# Sheet1.net
KiCad netlist of a schematic drawn in Altium Designer
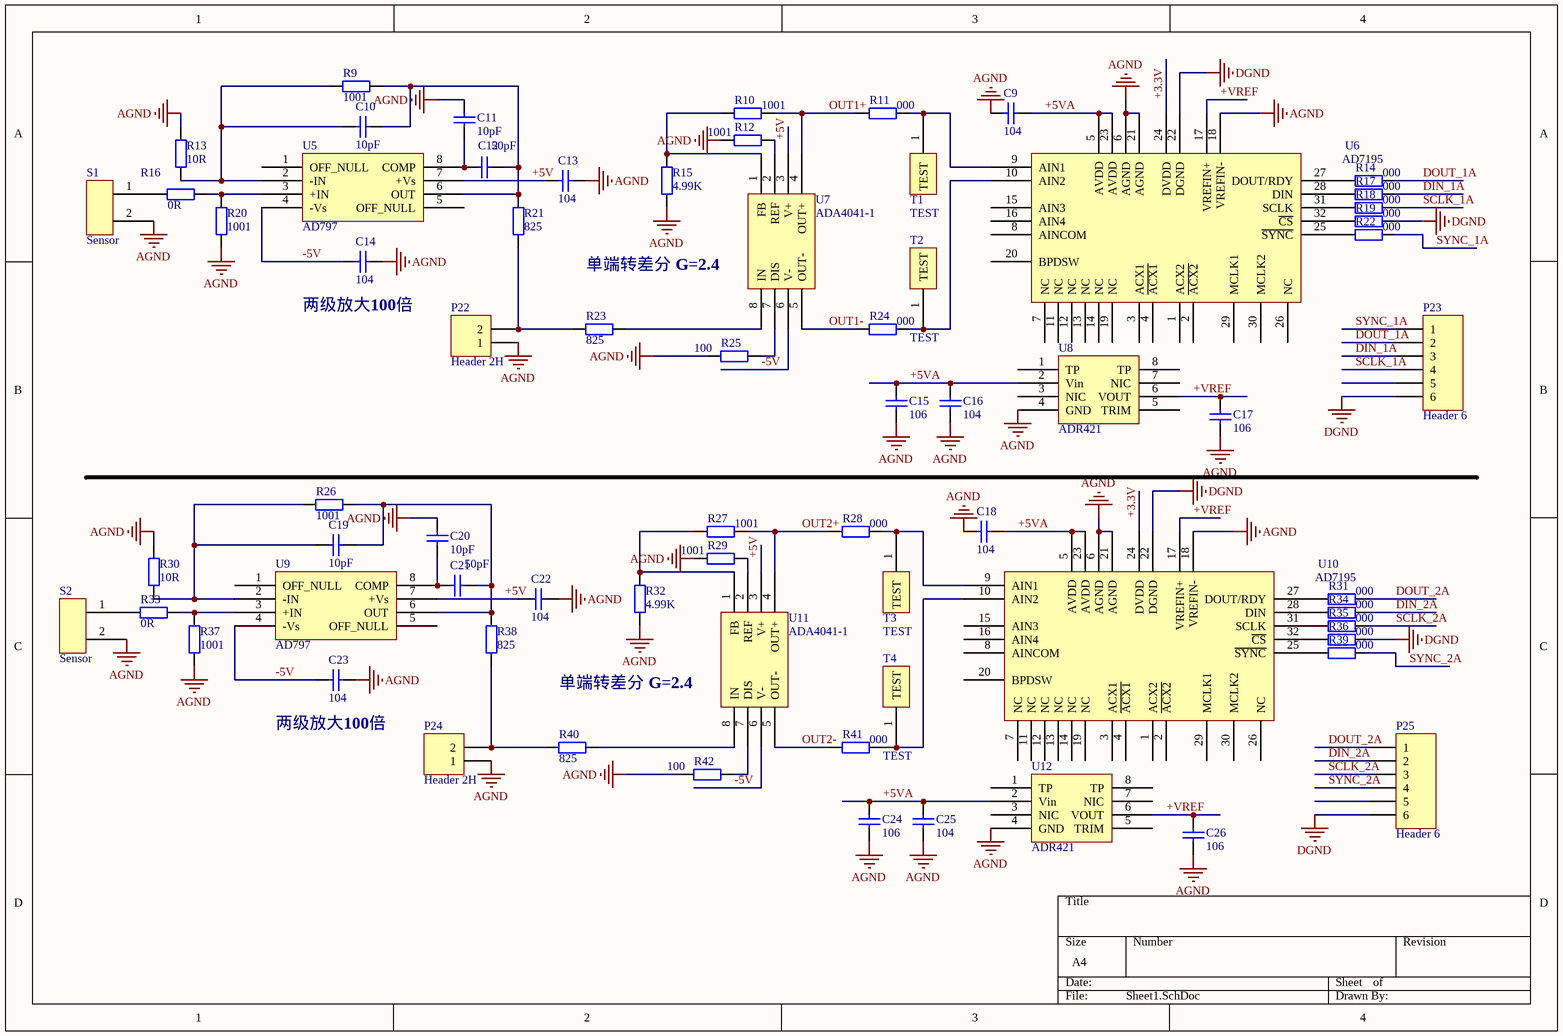
[diagram p0: Sheet1.SchDoc]

(export (version "E")
  (design (tool "Eeschema 10.0.6"))
  (components
    (comp (ref "C9")
      (value "104")
      (footprint "0805C")
      (description "Capacitor")
      (fields (field (name "PUBLISHER") "Altium Limited"))
      (libsource (lib "Miscellaneous Devices") (part "Cap"))
    )
    (comp (ref "C10")
      (value "10pF")
      (footprint "0805C")
      (description "Capacitor")
      (fields (field (name "PUBLISHER") "Altium Limited"))
      (libsource (lib "Miscellaneous Devices") (part "Cap"))
    )
    (comp (ref "C11")
      (value "10pF")
      (footprint "0805C")
      (description "Capacitor")
      (fields (field (name "PUBLISHER") "Altium Limited"))
      (libsource (lib "Miscellaneous Devices") (part "Cap"))
    )
    (comp (ref "C12")
      (value "50pF")
      (footprint "0805C")
      (description "Capacitor")
      (fields (field (name "PUBLISHER") "Altium Limited"))
      (libsource (lib "Miscellaneous Devices") (part "Cap"))
    )
    (comp (ref "C13")
      (value "104")
      (footprint "0805C")
      (description "Capacitor")
      (fields (field (name "PUBLISHER") "Altium Limited"))
      (libsource (lib "Miscellaneous Devices") (part "Cap"))
    )
    (comp (ref "C14")
      (value "104")
      (footprint "0805C")
      (description "Capacitor")
      (fields (field (name "PUBLISHER") "Altium Limited"))
      (libsource (lib "Miscellaneous Devices") (part "Cap"))
    )
    (comp (ref "C15")
      (value "106")
      (footprint "0805C")
      (description "Capacitor")
      (fields (field (name "PUBLISHER") "Altium Limited"))
      (libsource (lib "Miscellaneous Devices") (part "Cap"))
    )
    (comp (ref "C16")
      (value "104")
      (footprint "0805C")
      (description "Capacitor")
      (fields (field (name "PUBLISHER") "Altium Limited"))
      (libsource (lib "Miscellaneous Devices") (part "Cap"))
    )
    (comp (ref "C17")
      (value "106")
      (footprint "0805C")
      (description "Capacitor")
      (fields (field (name "PUBLISHER") "Altium Limited"))
      (libsource (lib "Miscellaneous Devices") (part "Cap"))
    )
    (comp (ref "C18")
      (value "104")
      (footprint "0805C")
      (description "Capacitor")
      (fields (field (name "PUBLISHER") "Altium Limited"))
      (libsource (lib "Miscellaneous Devices") (part "Cap"))
    )
    (comp (ref "C19")
      (value "10pF")
      (footprint "0805C")
      (description "Capacitor")
      (fields (field (name "PUBLISHER") "Altium Limited"))
      (libsource (lib "Miscellaneous Devices") (part "Cap"))
    )
    (comp (ref "C20")
      (value "10pF")
      (footprint "0805C")
      (description "Capacitor")
      (fields (field (name "PUBLISHER") "Altium Limited"))
      (libsource (lib "Miscellaneous Devices") (part "Cap"))
    )
    (comp (ref "C21")
      (value "50pF")
      (footprint "0805C")
      (description "Capacitor")
      (fields (field (name "PUBLISHER") "Altium Limited"))
      (libsource (lib "Miscellaneous Devices") (part "Cap"))
    )
    (comp (ref "C22")
      (value "104")
      (footprint "0805C")
      (description "Capacitor")
      (fields (field (name "PUBLISHER") "Altium Limited"))
      (libsource (lib "Miscellaneous Devices") (part "Cap"))
    )
    (comp (ref "C23")
      (value "104")
      (footprint "0805C")
      (description "Capacitor")
      (fields (field (name "PUBLISHER") "Altium Limited"))
      (libsource (lib "Miscellaneous Devices") (part "Cap"))
    )
    (comp (ref "C24")
      (value "106")
      (footprint "0805C")
      (description "Capacitor")
      (fields (field (name "PUBLISHER") "Altium Limited"))
      (libsource (lib "Miscellaneous Devices") (part "Cap"))
    )
    (comp (ref "C25")
      (value "104")
      (footprint "0805C")
      (description "Capacitor")
      (fields (field (name "PUBLISHER") "Altium Limited"))
      (libsource (lib "Miscellaneous Devices") (part "Cap"))
    )
    (comp (ref "C26")
      (value "106")
      (footprint "0805C")
      (description "Capacitor")
      (fields (field (name "PUBLISHER") "Altium Limited"))
      (libsource (lib "Miscellaneous Devices") (part "Cap"))
    )
    (comp (ref "P22")
      (value "Header 2H")
      (footprint "HDR1X2")
      (description "Header, 2-Pin, Right Angle")
      (fields (field (name "PUBLISHER") "Altium Limited"))
      (libsource (lib "Miscellaneous Connectors") (part "Header 2H"))
    )
    (comp (ref "P23")
      (value "Header 6")
      (footprint "HDR1X6")
      (description "Header, 6-Pin")
      (fields (field (name "PUBLISHER") "Altium Limited"))
      (libsource (lib "Miscellaneous Connectors") (part "Header 6"))
    )
    (comp (ref "P24")
      (value "Header 2H")
      (footprint "HDR1X2")
      (description "Header, 2-Pin, Right Angle")
      (fields (field (name "PUBLISHER") "Altium Limited"))
      (libsource (lib "Miscellaneous Connectors") (part "Header 2H"))
    )
    (comp (ref "P25")
      (value "Header 6")
      (footprint "HDR1X6")
      (description "Header, 6-Pin")
      (fields (field (name "PUBLISHER") "Altium Limited"))
      (libsource (lib "Miscellaneous Connectors") (part "Header 6"))
    )
    (comp (ref "R9")
      (value "1001")
      (footprint "0805R")
      (description "Resistor")
      (fields (field (name "PUBLISHER") "Altium Limited"))
      (libsource (lib "Miscellaneous Devices") (part "Res2"))
    )
    (comp (ref "R10")
      (value "1001")
      (footprint "0805R")
      (description "Resistor")
      (fields (field (name "PUBLISHER") "Altium Limited"))
      (libsource (lib "Miscellaneous Devices") (part "Res2"))
    )
    (comp (ref "R11")
      (value "000")
      (footprint "0805R")
      (description "Resistor")
      (fields (field (name "PUBLISHER") "Altium Limited"))
      (libsource (lib "Miscellaneous Devices") (part "Res2"))
    )
    (comp (ref "R12")
      (value "1001")
      (footprint "0805R")
      (description "Resistor")
      (fields (field (name "PUBLISHER") "Altium Limited"))
      (libsource (lib "Miscellaneous Devices") (part "Res2"))
    )
    (comp (ref "R13")
      (value "10R")
      (footprint "0805R")
      (description "Resistor")
      (fields (field (name "PUBLISHER") "Altium Limited"))
      (libsource (lib "") (part "Res2_1"))
    )
    (comp (ref "R14")
      (value "000")
      (footprint "0805R")
      (description "Resistor")
      (fields (field (name "PUBLISHER") "Altium Limited"))
      (libsource (lib "Miscellaneous Devices") (part "Res2"))
    )
    (comp (ref "R15")
      (value "4.99K")
      (footprint "0805R")
      (description "Resistor")
      (fields (field (name "PUBLISHER") "Altium Limited"))
      (libsource (lib "") (part "Res2_2"))
    )
    (comp (ref "R16")
      (value "0R")
      (footprint "0805R")
      (description "Resistor")
      (fields (field (name "PUBLISHER") "Altium Limited"))
      (libsource (lib "Miscellaneous Devices") (part "Res2"))
    )
    (comp (ref "R17")
      (value "000")
      (footprint "0805R")
      (description "Resistor")
      (fields (field (name "PUBLISHER") "Altium Limited"))
      (libsource (lib "Miscellaneous Devices") (part "Res2"))
    )
    (comp (ref "R18")
      (value "000")
      (footprint "0805R")
      (description "Resistor")
      (fields (field (name "PUBLISHER") "Altium Limited"))
      (libsource (lib "Miscellaneous Devices") (part "Res2"))
    )
    (comp (ref "R19")
      (value "000")
      (footprint "0805R")
      (description "Resistor")
      (fields (field (name "PUBLISHER") "Altium Limited"))
      (libsource (lib "Miscellaneous Devices") (part "Res2"))
    )
    (comp (ref "R20")
      (value "1001")
      (footprint "0805R")
      (description "Resistor")
      (fields (field (name "PUBLISHER") "Altium Limited"))
      (libsource (lib "") (part "Res2_2"))
    )
    (comp (ref "R21")
      (value "825")
      (footprint "0805R")
      (description "Resistor")
      (fields (field (name "PUBLISHER") "Altium Limited"))
      (libsource (lib "") (part "Res2_2"))
    )
    (comp (ref "R22")
      (value "000")
      (footprint "0805R")
      (description "Resistor")
      (fields (field (name "PUBLISHER") "Altium Limited"))
      (libsource (lib "Miscellaneous Devices") (part "Res2"))
    )
    (comp (ref "R23")
      (value "825")
      (footprint "0805R")
      (description "Resistor")
      (fields (field (name "PUBLISHER") "Altium Limited"))
      (libsource (lib "Miscellaneous Devices") (part "Res2"))
    )
    (comp (ref "R24")
      (value "000")
      (footprint "0805R")
      (description "Resistor")
      (fields (field (name "PUBLISHER") "Altium Limited"))
      (libsource (lib "Miscellaneous Devices") (part "Res2"))
    )
    (comp (ref "R25")
      (value "100")
      (footprint "0805R")
      (description "Resistor")
      (fields (field (name "PUBLISHER") "Altium Limited"))
      (libsource (lib "Miscellaneous Devices") (part "Res2"))
    )
    (comp (ref "R26")
      (value "1001")
      (footprint "0805R")
      (description "Resistor")
      (fields (field (name "PUBLISHER") "Altium Limited"))
      (libsource (lib "Miscellaneous Devices") (part "Res2"))
    )
    (comp (ref "R27")
      (value "1001")
      (footprint "0805R")
      (description "Resistor")
      (fields (field (name "PUBLISHER") "Altium Limited"))
      (libsource (lib "Miscellaneous Devices") (part "Res2"))
    )
    (comp (ref "R28")
      (value "000")
      (footprint "0805R")
      (description "Resistor")
      (fields (field (name "PUBLISHER") "Altium Limited"))
      (libsource (lib "Miscellaneous Devices") (part "Res2"))
    )
    (comp (ref "R29")
      (value "1001")
      (footprint "0805R")
      (description "Resistor")
      (fields (field (name "PUBLISHER") "Altium Limited"))
      (libsource (lib "Miscellaneous Devices") (part "Res2"))
    )
    (comp (ref "R30")
      (value "10R")
      (footprint "0805R")
      (description "Resistor")
      (fields (field (name "PUBLISHER") "Altium Limited"))
      (libsource (lib "") (part "Res2_1"))
    )
    (comp (ref "R31")
      (value "000")
      (footprint "0805R")
      (description "Resistor")
      (fields (field (name "PUBLISHER") "Altium Limited"))
      (libsource (lib "Miscellaneous Devices") (part "Res2"))
    )
    (comp (ref "R32")
      (value "4.99K")
      (footprint "0805R")
      (description "Resistor")
      (fields (field (name "PUBLISHER") "Altium Limited"))
      (libsource (lib "") (part "Res2_2"))
    )
    (comp (ref "R33")
      (value "0R")
      (footprint "0805R")
      (description "Resistor")
      (fields (field (name "PUBLISHER") "Altium Limited"))
      (libsource (lib "Miscellaneous Devices") (part "Res2"))
    )
    (comp (ref "R34")
      (value "000")
      (footprint "0805R")
      (description "Resistor")
      (fields (field (name "PUBLISHER") "Altium Limited"))
      (libsource (lib "Miscellaneous Devices") (part "Res2"))
    )
    (comp (ref "R35")
      (value "000")
      (footprint "0805R")
      (description "Resistor")
      (fields (field (name "PUBLISHER") "Altium Limited"))
      (libsource (lib "Miscellaneous Devices") (part "Res2"))
    )
    (comp (ref "R36")
      (value "000")
      (footprint "0805R")
      (description "Resistor")
      (fields (field (name "PUBLISHER") "Altium Limited"))
      (libsource (lib "Miscellaneous Devices") (part "Res2"))
    )
    (comp (ref "R37")
      (value "1001")
      (footprint "0805R")
      (description "Resistor")
      (fields (field (name "PUBLISHER") "Altium Limited"))
      (libsource (lib "") (part "Res2_2"))
    )
    (comp (ref "R38")
      (value "825")
      (footprint "0805R")
      (description "Resistor")
      (fields (field (name "PUBLISHER") "Altium Limited"))
      (libsource (lib "") (part "Res2_2"))
    )
    (comp (ref "R39")
      (value "000")
      (footprint "0805R")
      (description "Resistor")
      (fields (field (name "PUBLISHER") "Altium Limited"))
      (libsource (lib "Miscellaneous Devices") (part "Res2"))
    )
    (comp (ref "R40")
      (value "825")
      (footprint "0805R")
      (description "Resistor")
      (fields (field (name "PUBLISHER") "Altium Limited"))
      (libsource (lib "Miscellaneous Devices") (part "Res2"))
    )
    (comp (ref "R41")
      (value "000")
      (footprint "0805R")
      (description "Resistor")
      (fields (field (name "PUBLISHER") "Altium Limited"))
      (libsource (lib "Miscellaneous Devices") (part "Res2"))
    )
    (comp (ref "R42")
      (value "100")
      (footprint "0805R")
      (description "Resistor")
      (fields (field (name "PUBLISHER") "Altium Limited"))
      (libsource (lib "Miscellaneous Devices") (part "Res2"))
    )
    (comp (ref "S1") (value "Sensor") (footprint "HDR1X2") (libsource (lib "Schlib1") (part "Sensor")))
    (comp (ref "S2") (value "Sensor") (footprint "HDR1X2") (libsource (lib "Schlib1") (part "Sensor")))
    (comp (ref "T1") (value "TEST") (footprint "TEST") (libsource (lib "Schlib1") (part "TEST")))
    (comp (ref "T2") (value "TEST") (footprint "TEST") (libsource (lib "") (part "TEST_1")))
    (comp (ref "T3") (value "TEST") (footprint "TEST") (libsource (lib "Schlib1") (part "TEST")))
    (comp (ref "T4") (value "TEST") (footprint "TEST") (libsource (lib "") (part "TEST_1")))
    (comp (ref "U5") (value "AD797") (footprint "SO8") (libsource (lib "Schlib1") (part "AD797")))
    (comp (ref "U6") (value "AD7195") (footprint "LFCSP32") (libsource (lib "Schlib1") (part "AD7195")))
    (comp (ref "U7") (value "ADA4041-1") (footprint "SO8") (libsource (lib "Schlib1") (part "ADA4041-1")))
    (comp (ref "U8") (value "ADR421") (footprint "SO8") (libsource (lib "Schlib1") (part "ADR421")))
    (comp (ref "U9") (value "AD797") (footprint "SO8") (libsource (lib "Schlib1") (part "AD797")))
    (comp (ref "U10") (value "AD7195") (footprint "LFCSP32") (libsource (lib "Schlib1") (part "AD7195")))
    (comp (ref "U11") (value "ADA4041-1") (footprint "SO8") (libsource (lib "Schlib1") (part "ADA4041-1")))
    (comp (ref "U12") (value "ADR421") (footprint "SO8") (libsource (lib "Schlib1") (part "ADR421")))
  )
  (nets
    (net (code "1") (name "/+3.3V") (class "Default")
      (node (ref "U10") (pin "24") (pinfunction "DVDD_24") (pintype "passive"))
      (node (ref "U6") (pin "24") (pinfunction "DVDD_24") (pintype "passive"))
    )
    (net (code "2") (name "/+5V") (class "Default")
      (node (ref "C13") (pin "2") (pinfunction "2_2") (pintype "passive"))
      (node (ref "C22") (pin "2") (pinfunction "2_2") (pintype "passive"))
      (node (ref "U11") (pin "3") (pinfunction "V+_3") (pintype "passive"))
      (node (ref "U5") (pin "7") (pinfunction "+Vs_7") (pintype "passive"))
      (node (ref "U7") (pin "3") (pinfunction "V+_3") (pintype "passive"))
      (node (ref "U9") (pin "7") (pinfunction "+Vs_7") (pintype "passive"))
    )
    (net (code "3") (name "/+5VA") (class "Default")
      (node (ref "C15") (pin "1") (pinfunction "1_1") (pintype "passive"))
      (node (ref "C16") (pin "1") (pinfunction "1_1") (pintype "passive"))
      (node (ref "C18") (pin "2") (pinfunction "2_2") (pintype "passive"))
      (node (ref "C24") (pin "1") (pinfunction "1_1") (pintype "passive"))
      (node (ref "C25") (pin "1") (pinfunction "1_1") (pintype "passive"))
      (node (ref "C9") (pin "2") (pinfunction "2_2") (pintype "passive"))
      (node (ref "U10") (pin "23") (pinfunction "AVDD_23") (pintype "passive"))
      (node (ref "U10") (pin "5") (pinfunction "AVDD_5") (pintype "passive"))
      (node (ref "U12") (pin "2") (pinfunction "Vin_2") (pintype "passive"))
      (node (ref "U6") (pin "23") (pinfunction "AVDD_23") (pintype "passive"))
      (node (ref "U6") (pin "5") (pinfunction "AVDD_5") (pintype "passive"))
      (node (ref "U8") (pin "2") (pinfunction "Vin_2") (pintype "passive"))
    )
    (net (code "4") (name "/+VREF") (class "Default")
      (node (ref "C17") (pin "1") (pinfunction "1_1") (pintype "passive"))
      (node (ref "C26") (pin "1") (pinfunction "1_1") (pintype "passive"))
      (node (ref "U10") (pin "17") (pinfunction "VREFIN+_17") (pintype "passive"))
      (node (ref "U12") (pin "6") (pinfunction "VOUT_6") (pintype "passive"))
      (node (ref "U6") (pin "17") (pinfunction "VREFIN+_17") (pintype "passive"))
      (node (ref "U8") (pin "6") (pinfunction "VOUT_6") (pintype "passive"))
    )
    (net (code "5") (name "/-5V") (class "Default")
      (node (ref "C14") (pin "2") (pinfunction "2_2") (pintype "passive"))
      (node (ref "C23") (pin "2") (pinfunction "2_2") (pintype "passive"))
      (node (ref "U11") (pin "6") (pinfunction "V-_6") (pintype "passive"))
      (node (ref "U5") (pin "4") (pinfunction "-Vs_4") (pintype "passive"))
      (node (ref "U7") (pin "6") (pinfunction "V-_6") (pintype "passive"))
      (node (ref "U9") (pin "4") (pinfunction "-Vs_4") (pintype "passive"))
    )
    (net (code "6") (name "/DIN_1A") (class "Default")
      (node (ref "P23") (pin "3") (pinfunction "3_3") (pintype "passive"))
      (node (ref "R17") (pin "2") (pinfunction "2_2") (pintype "passive"))
    )
    (net (code "7") (name "/DIN_2A") (class "Default")
      (node (ref "P25") (pin "2") (pinfunction "2_2") (pintype "passive"))
      (node (ref "R34") (pin "2") (pinfunction "2_2") (pintype "passive"))
    )
    (net (code "8") (name "/DOUT_1A") (class "Default")
      (node (ref "P23") (pin "2") (pinfunction "2_2") (pintype "passive"))
      (node (ref "R14") (pin "2") (pinfunction "2_2") (pintype "passive"))
    )
    (net (code "9") (name "/DOUT_2A") (class "Default")
      (node (ref "P25") (pin "1") (pinfunction "1_1") (pintype "passive"))
      (node (ref "R31") (pin "2") (pinfunction "2_2") (pintype "passive"))
    )
    (net (code "10") (name "/OUT1+") (class "Default")
      (node (ref "R10") (pin "2") (pinfunction "2_2") (pintype "passive"))
      (node (ref "R11") (pin "1") (pinfunction "1_1") (pintype "passive"))
      (node (ref "U7") (pin "4") (pinfunction "OUT+_4") (pintype "passive"))
    )
    (net (code "11") (name "/OUT1-") (class "Default")
      (node (ref "R24") (pin "1") (pinfunction "1_1") (pintype "passive"))
      (node (ref "U7") (pin "5") (pinfunction "OUT-_5") (pintype "passive"))
    )
    (net (code "12") (name "/OUT2+") (class "Default")
      (node (ref "R27") (pin "2") (pinfunction "2_2") (pintype "passive"))
      (node (ref "R28") (pin "1") (pinfunction "1_1") (pintype "passive"))
      (node (ref "U11") (pin "4") (pinfunction "OUT+_4") (pintype "passive"))
    )
    (net (code "13") (name "/OUT2-") (class "Default")
      (node (ref "R41") (pin "1") (pinfunction "1_1") (pintype "passive"))
      (node (ref "U11") (pin "5") (pinfunction "OUT-_5") (pintype "passive"))
    )
    (net (code "14") (name "/SCLK_1A") (class "Default")
      (node (ref "P23") (pin "4") (pinfunction "4_4") (pintype "passive"))
      (node (ref "R18") (pin "2") (pinfunction "2_2") (pintype "passive"))
    )
    (net (code "15") (name "/SCLK_2A") (class "Default")
      (node (ref "P25") (pin "3") (pinfunction "3_3") (pintype "passive"))
      (node (ref "R35") (pin "2") (pinfunction "2_2") (pintype "passive"))
    )
    (net (code "16") (name "/SYNC_1A") (class "Default")
      (node (ref "P23") (pin "1") (pinfunction "1_1") (pintype "passive"))
      (node (ref "R22") (pin "2") (pinfunction "2_2") (pintype "passive"))
    )
    (net (code "17") (name "/SYNC_2A") (class "Default")
      (node (ref "P25") (pin "4") (pinfunction "4_4") (pintype "passive"))
      (node (ref "R39") (pin "2") (pinfunction "2_2") (pintype "passive"))
    )
    (net (code "18") (name "AGND") (class "Default")
      (node (ref "C11") (pin "2") (pinfunction "2_2") (pintype "passive"))
      (node (ref "C13") (pin "1") (pinfunction "1_1") (pintype "passive"))
      (node (ref "C14") (pin "1") (pinfunction "1_1") (pintype "passive"))
      (node (ref "C15") (pin "2") (pinfunction "2_2") (pintype "passive"))
      (node (ref "C16") (pin "2") (pinfunction "2_2") (pintype "passive"))
      (node (ref "C17") (pin "2") (pinfunction "2_2") (pintype "passive"))
      (node (ref "C18") (pin "1") (pinfunction "1_1") (pintype "passive"))
      (node (ref "C20") (pin "2") (pinfunction "2_2") (pintype "passive"))
      (node (ref "C22") (pin "1") (pinfunction "1_1") (pintype "passive"))
      (node (ref "C23") (pin "1") (pinfunction "1_1") (pintype "passive"))
      (node (ref "C24") (pin "2") (pinfunction "2_2") (pintype "passive"))
      (node (ref "C25") (pin "2") (pinfunction "2_2") (pintype "passive"))
      (node (ref "C26") (pin "2") (pinfunction "2_2") (pintype "passive"))
      (node (ref "C9") (pin "1") (pinfunction "1_1") (pintype "passive"))
      (node (ref "P22") (pin "1") (pinfunction "1_1") (pintype "passive"))
      (node (ref "P24") (pin "1") (pinfunction "1_1") (pintype "passive"))
      (node (ref "R12") (pin "1") (pinfunction "1_1") (pintype "passive"))
      (node (ref "R13") (pin "1") (pinfunction "1_1") (pintype "passive"))
      (node (ref "R15") (pin "1") (pinfunction "1_1") (pintype "passive"))
      (node (ref "R20") (pin "1") (pinfunction "1_1") (pintype "passive"))
      (node (ref "R25") (pin "1") (pinfunction "1_1") (pintype "passive"))
      (node (ref "R29") (pin "1") (pinfunction "1_1") (pintype "passive"))
      (node (ref "R30") (pin "1") (pinfunction "1_1") (pintype "passive"))
      (node (ref "R32") (pin "1") (pinfunction "1_1") (pintype "passive"))
      (node (ref "R37") (pin "1") (pinfunction "1_1") (pintype "passive"))
      (node (ref "R42") (pin "1") (pinfunction "1_1") (pintype "passive"))
      (node (ref "S1") (pin "2") (pinfunction "2_2") (pintype "passive"))
      (node (ref "S2") (pin "2") (pinfunction "2_2") (pintype "passive"))
      (node (ref "U10") (pin "18") (pinfunction "VREFIN-_18") (pintype "passive"))
      (node (ref "U10") (pin "21") (pinfunction "AGND_21") (pintype "passive"))
      (node (ref "U10") (pin "6") (pinfunction "AGND_6") (pintype "passive"))
      (node (ref "U12") (pin "4") (pinfunction "GND_4") (pintype "passive"))
      (node (ref "U6") (pin "18") (pinfunction "VREFIN-_18") (pintype "passive"))
      (node (ref "U6") (pin "21") (pinfunction "AGND_21") (pintype "passive"))
      (node (ref "U6") (pin "6") (pinfunction "AGND_6") (pintype "passive"))
      (node (ref "U8") (pin "4") (pinfunction "GND_4") (pintype "passive"))
    )
    (net (code "19") (name "DGND") (class "Default")
      (node (ref "P23") (pin "6") (pinfunction "6_6") (pintype "passive"))
      (node (ref "P25") (pin "6") (pinfunction "6_6") (pintype "passive"))
      (node (ref "R19") (pin "2") (pinfunction "2_2") (pintype "passive"))
      (node (ref "R36") (pin "2") (pinfunction "2_2") (pintype "passive"))
      (node (ref "U10") (pin "22") (pinfunction "DGND_22") (pintype "passive"))
      (node (ref "U6") (pin "22") (pinfunction "DGND_22") (pintype "passive"))
    )
    (net (code "20") (name "Net-(P22-Pad2)") (class "Default")
      (node (ref "P22") (pin "2") (pinfunction "2_2") (pintype "passive"))
      (node (ref "R21") (pin "1") (pinfunction "1_1") (pintype "passive"))
      (node (ref "R23") (pin "1") (pinfunction "1_1") (pintype "passive"))
    )
    (net (code "21") (name "Net-(P24-Pad2)") (class "Default")
      (node (ref "P24") (pin "2") (pinfunction "2_2") (pintype "passive"))
      (node (ref "R38") (pin "1") (pinfunction "1_1") (pintype "passive"))
      (node (ref "R40") (pin "1") (pinfunction "1_1") (pintype "passive"))
    )
    (net (code "22") (name "Net-(R16-Pad1)") (class "Default")
      (node (ref "R16") (pin "1") (pinfunction "1_1") (pintype "passive"))
      (node (ref "S1") (pin "1") (pinfunction "1_1") (pintype "passive"))
    )
    (net (code "23") (name "Net-(R33-Pad1)") (class "Default")
      (node (ref "R33") (pin "1") (pinfunction "1_1") (pintype "passive"))
      (node (ref "S2") (pin "1") (pinfunction "1_1") (pintype "passive"))
    )
    (net (code "24") (name "Net-(T1-TEST)") (class "Default")
      (node (ref "R11") (pin "2") (pinfunction "2_2") (pintype "passive"))
      (node (ref "T1") (pin "1") (pinfunction "TEST_1") (pintype "passive"))
      (node (ref "U6") (pin "9") (pinfunction "AIN1_9") (pintype "passive"))
    )
    (net (code "25") (name "Net-(T2-TEST)") (class "Default")
      (node (ref "R24") (pin "2") (pinfunction "2_2") (pintype "passive"))
      (node (ref "T2") (pin "1") (pinfunction "TEST_1") (pintype "passive"))
      (node (ref "U6") (pin "10") (pinfunction "AIN2_10") (pintype "passive"))
    )
    (net (code "26") (name "Net-(T3-TEST)") (class "Default")
      (node (ref "R28") (pin "2") (pinfunction "2_2") (pintype "passive"))
      (node (ref "T3") (pin "1") (pinfunction "TEST_1") (pintype "passive"))
      (node (ref "U10") (pin "9") (pinfunction "AIN1_9") (pintype "passive"))
    )
    (net (code "27") (name "Net-(T4-TEST)") (class "Default")
      (node (ref "R41") (pin "2") (pinfunction "2_2") (pintype "passive"))
      (node (ref "T4") (pin "1") (pinfunction "TEST_1") (pintype "passive"))
      (node (ref "U10") (pin "10") (pinfunction "AIN2_10") (pintype "passive"))
    )
    (net (code "28") (name "Net-(U5-+IN)") (class "Default")
      (node (ref "R16") (pin "2") (pinfunction "2_2") (pintype "passive"))
      (node (ref "R20") (pin "2") (pinfunction "2_2") (pintype "passive"))
      (node (ref "U5") (pin "3") (pinfunction "+IN_3") (pintype "passive"))
    )
    (net (code "29") (name "Net-(U5--IN)") (class "Default")
      (node (ref "C10") (pin "2") (pinfunction "2_2") (pintype "passive"))
      (node (ref "R13") (pin "2") (pinfunction "2_2") (pintype "passive"))
      (node (ref "R9") (pin "1") (pinfunction "1_1") (pintype "passive"))
      (node (ref "U5") (pin "2") (pinfunction "-IN_2") (pintype "passive"))
    )
    (net (code "30") (name "Net-(U5-COMP)") (class "Default")
      (node (ref "C11") (pin "1") (pinfunction "1_1") (pintype "passive"))
      (node (ref "C12") (pin "2") (pinfunction "2_2") (pintype "passive"))
      (node (ref "U5") (pin "8") (pinfunction "COMP_8") (pintype "passive"))
    )
    (net (code "31") (name "Net-(U5-OUT)") (class "Default")
      (node (ref "C10") (pin "1") (pinfunction "1_1") (pintype "passive"))
      (node (ref "C12") (pin "1") (pinfunction "1_1") (pintype "passive"))
      (node (ref "R21") (pin "2") (pinfunction "2_2") (pintype "passive"))
      (node (ref "R9") (pin "2") (pinfunction "2_2") (pintype "passive"))
      (node (ref "U5") (pin "6") (pinfunction "OUT_6") (pintype "passive"))
    )
    (net (code "32") (name "Net-(U6-DIN)") (class "Default")
      (node (ref "R17") (pin "1") (pinfunction "1_1") (pintype "passive"))
      (node (ref "U6") (pin "28") (pinfunction "DIN_28") (pintype "passive"))
    )
    (net (code "33") (name "Net-(U6-DOUT{slash}RDY)") (class "Default")
      (node (ref "R14") (pin "1") (pinfunction "1_1") (pintype "passive"))
      (node (ref "U6") (pin "27") (pinfunction "DOUT/RDY_27") (pintype "passive"))
    )
    (net (code "34") (name "Net-(U6-SCLK)") (class "Default")
      (node (ref "R18") (pin "1") (pinfunction "1_1") (pintype "passive"))
      (node (ref "U6") (pin "31") (pinfunction "SCLK_31") (pintype "passive"))
    )
    (net (code "35") (name "Net-(U6-~{CS})") (class "Default")
      (node (ref "R19") (pin "1") (pinfunction "1_1") (pintype "passive"))
      (node (ref "U6") (pin "32") (pinfunction "~{CS}_32") (pintype "passive"))
    )
    (net (code "36") (name "Net-(U6-~{SYNC})") (class "Default")
      (node (ref "R22") (pin "1") (pinfunction "1_1") (pintype "passive"))
      (node (ref "U6") (pin "25") (pinfunction "~{SYNC}_25") (pintype "passive"))
    )
    (net (code "37") (name "Net-(U7-DIS)") (class "Default")
      (node (ref "R25") (pin "2") (pinfunction "2_2") (pintype "passive"))
      (node (ref "U7") (pin "7") (pinfunction "DIS_7") (pintype "passive"))
    )
    (net (code "38") (name "Net-(U7-FB)") (class "Default")
      (node (ref "R10") (pin "1") (pinfunction "1_1") (pintype "passive"))
      (node (ref "R15") (pin "2") (pinfunction "2_2") (pintype "passive"))
      (node (ref "U7") (pin "1") (pinfunction "FB_1") (pintype "passive"))
    )
    (net (code "39") (name "Net-(U7-IN)") (class "Default")
      (node (ref "R23") (pin "2") (pinfunction "2_2") (pintype "passive"))
      (node (ref "U7") (pin "8") (pinfunction "IN_8") (pintype "passive"))
    )
    (net (code "40") (name "Net-(U7-REF)") (class "Default")
      (node (ref "R12") (pin "2") (pinfunction "2_2") (pintype "passive"))
      (node (ref "U7") (pin "2") (pinfunction "REF_2") (pintype "passive"))
    )
    (net (code "41") (name "Net-(U9-+IN)") (class "Default")
      (node (ref "R33") (pin "2") (pinfunction "2_2") (pintype "passive"))
      (node (ref "R37") (pin "2") (pinfunction "2_2") (pintype "passive"))
      (node (ref "U9") (pin "3") (pinfunction "+IN_3") (pintype "passive"))
    )
    (net (code "42") (name "Net-(U9--IN)") (class "Default")
      (node (ref "C19") (pin "2") (pinfunction "2_2") (pintype "passive"))
      (node (ref "R26") (pin "1") (pinfunction "1_1") (pintype "passive"))
      (node (ref "R30") (pin "2") (pinfunction "2_2") (pintype "passive"))
      (node (ref "U9") (pin "2") (pinfunction "-IN_2") (pintype "passive"))
    )
    (net (code "43") (name "Net-(U9-COMP)") (class "Default")
      (node (ref "C20") (pin "1") (pinfunction "1_1") (pintype "passive"))
      (node (ref "C21") (pin "2") (pinfunction "2_2") (pintype "passive"))
      (node (ref "U9") (pin "8") (pinfunction "COMP_8") (pintype "passive"))
    )
    (net (code "44") (name "Net-(U9-OUT)") (class "Default")
      (node (ref "C19") (pin "1") (pinfunction "1_1") (pintype "passive"))
      (node (ref "C21") (pin "1") (pinfunction "1_1") (pintype "passive"))
      (node (ref "R26") (pin "2") (pinfunction "2_2") (pintype "passive"))
      (node (ref "R38") (pin "2") (pinfunction "2_2") (pintype "passive"))
      (node (ref "U9") (pin "6") (pinfunction "OUT_6") (pintype "passive"))
    )
    (net (code "45") (name "Net-(U10-DIN)") (class "Default")
      (node (ref "R34") (pin "1") (pinfunction "1_1") (pintype "passive"))
      (node (ref "U10") (pin "28") (pinfunction "DIN_28") (pintype "passive"))
    )
    (net (code "46") (name "Net-(U10-DOUT{slash}RDY)") (class "Default")
      (node (ref "R31") (pin "1") (pinfunction "1_1") (pintype "passive"))
      (node (ref "U10") (pin "27") (pinfunction "DOUT/RDY_27") (pintype "passive"))
    )
    (net (code "47") (name "Net-(U10-SCLK)") (class "Default")
      (node (ref "R35") (pin "1") (pinfunction "1_1") (pintype "passive"))
      (node (ref "U10") (pin "31") (pinfunction "SCLK_31") (pintype "passive"))
    )
    (net (code "48") (name "Net-(U10-~{CS})") (class "Default")
      (node (ref "R36") (pin "1") (pinfunction "1_1") (pintype "passive"))
      (node (ref "U10") (pin "32") (pinfunction "~{CS}_32") (pintype "passive"))
    )
    (net (code "49") (name "Net-(U10-~{SYNC})") (class "Default")
      (node (ref "R39") (pin "1") (pinfunction "1_1") (pintype "passive"))
      (node (ref "U10") (pin "25") (pinfunction "~{SYNC}_25") (pintype "passive"))
    )
    (net (code "50") (name "Net-(U11-DIS)") (class "Default")
      (node (ref "R42") (pin "2") (pinfunction "2_2") (pintype "passive"))
      (node (ref "U11") (pin "7") (pinfunction "DIS_7") (pintype "passive"))
    )
    (net (code "51") (name "Net-(U11-FB)") (class "Default")
      (node (ref "R27") (pin "1") (pinfunction "1_1") (pintype "passive"))
      (node (ref "R32") (pin "2") (pinfunction "2_2") (pintype "passive"))
      (node (ref "U11") (pin "1") (pinfunction "FB_1") (pintype "passive"))
    )
    (net (code "52") (name "Net-(U11-IN)") (class "Default")
      (node (ref "R40") (pin "2") (pinfunction "2_2") (pintype "passive"))
      (node (ref "U11") (pin "8") (pinfunction "IN_8") (pintype "passive"))
    )
    (net (code "53") (name "Net-(U11-REF)") (class "Default")
      (node (ref "R29") (pin "2") (pinfunction "2_2") (pintype "passive"))
      (node (ref "U11") (pin "2") (pinfunction "REF_2") (pintype "passive"))
    )
    (net (code "54") (name "unconnected-(P23-Pad5)") (class "Default")
      (node (ref "P23") (pin "5") (pinfunction "5_5") (pintype "passive"))
    )
    (net (code "55") (name "unconnected-(P25-Pad5)") (class "Default")
      (node (ref "P25") (pin "5") (pinfunction "5_5") (pintype "passive"))
    )
    (net (code "56") (name "unconnected-(U5-OFF_NULL-Pad1)") (class "Default")
      (node (ref "U5") (pin "1") (pinfunction "OFF_NULL_1") (pintype "passive"))
    )
    (net (code "57") (name "unconnected-(U5-OFF_NULL-Pad5)") (class "Default")
      (node (ref "U5") (pin "5") (pinfunction "OFF_NULL_5") (pintype "passive"))
    )
    (net (code "58") (name "unconnected-(U6-ACX1-Pad3)") (class "Default")
      (node (ref "U6") (pin "3") (pinfunction "ACX1_3") (pintype "passive"))
    )
    (net (code "59") (name "unconnected-(U6-ACX2-Pad1)") (class "Default")
      (node (ref "U6") (pin "1") (pinfunction "ACX2_1") (pintype "passive"))
    )
    (net (code "60") (name "unconnected-(U6-AIN3-Pad15)") (class "Default")
      (node (ref "U6") (pin "15") (pinfunction "AIN3_15") (pintype "passive"))
    )
    (net (code "61") (name "unconnected-(U6-AIN4-Pad16)") (class "Default")
      (node (ref "U6") (pin "16") (pinfunction "AIN4_16") (pintype "passive"))
    )
    (net (code "62") (name "unconnected-(U6-AINCOM-Pad8)") (class "Default")
      (node (ref "U6") (pin "8") (pinfunction "AINCOM_8") (pintype "passive"))
    )
    (net (code "63") (name "unconnected-(U6-BPDSW-Pad20)") (class "Default")
      (node (ref "U6") (pin "20") (pinfunction "BPDSW_20") (pintype "passive"))
    )
    (net (code "64") (name "unconnected-(U6-MCLK1-Pad29)") (class "Default")
      (node (ref "U6") (pin "29") (pinfunction "MCLK1_29") (pintype "passive"))
    )
    (net (code "65") (name "unconnected-(U6-MCLK2-Pad30)") (class "Default")
      (node (ref "U6") (pin "30") (pinfunction "MCLK2_30") (pintype "passive"))
    )
    (net (code "66") (name "unconnected-(U6-NC-Pad7)") (class "Default")
      (node (ref "U6") (pin "7") (pinfunction "NC_7") (pintype "passive"))
    )
    (net (code "67") (name "unconnected-(U6-NC-Pad11)") (class "Default")
      (node (ref "U6") (pin "11") (pinfunction "NC_11") (pintype "passive"))
    )
    (net (code "68") (name "unconnected-(U6-NC-Pad12)") (class "Default")
      (node (ref "U6") (pin "12") (pinfunction "NC_12") (pintype "passive"))
    )
    (net (code "69") (name "unconnected-(U6-NC-Pad13)") (class "Default")
      (node (ref "U6") (pin "13") (pinfunction "NC_13") (pintype "passive"))
    )
    (net (code "70") (name "unconnected-(U6-NC-Pad14)") (class "Default")
      (node (ref "U6") (pin "14") (pinfunction "NC_14") (pintype "passive"))
    )
    (net (code "71") (name "unconnected-(U6-NC-Pad19)") (class "Default")
      (node (ref "U6") (pin "19") (pinfunction "NC_19") (pintype "passive"))
    )
    (net (code "72") (name "unconnected-(U6-NC-Pad26)") (class "Default")
      (node (ref "U6") (pin "26") (pinfunction "NC_26") (pintype "passive"))
    )
    (net (code "73") (name "unconnected-(U6-~{ACX1}-Pad4)") (class "Default")
      (node (ref "U6") (pin "4") (pinfunction "~{ACX1}_4") (pintype "passive"))
    )
    (net (code "74") (name "unconnected-(U6-~{ACX2}-Pad2)") (class "Default")
      (node (ref "U6") (pin "2") (pinfunction "~{ACX2}_2") (pintype "passive"))
    )
    (net (code "75") (name "unconnected-(U8-NIC-Pad3)") (class "Default")
      (node (ref "U8") (pin "3") (pinfunction "NIC_3") (pintype "passive"))
    )
    (net (code "76") (name "unconnected-(U8-NIC-Pad7)") (class "Default")
      (node (ref "U8") (pin "7") (pinfunction "NIC_7") (pintype "passive"))
    )
    (net (code "77") (name "unconnected-(U8-TP-Pad1)") (class "Default")
      (node (ref "U8") (pin "1") (pinfunction "TP_1") (pintype "passive"))
    )
    (net (code "78") (name "unconnected-(U8-TP-Pad8)") (class "Default")
      (node (ref "U8") (pin "8") (pinfunction "TP_8") (pintype "passive"))
    )
    (net (code "79") (name "unconnected-(U8-TRIM-Pad5)") (class "Default")
      (node (ref "U8") (pin "5") (pinfunction "TRIM_5") (pintype "passive"))
    )
    (net (code "80") (name "unconnected-(U9-OFF_NULL-Pad1)") (class "Default")
      (node (ref "U9") (pin "1") (pinfunction "OFF_NULL_1") (pintype "passive"))
    )
    (net (code "81") (name "unconnected-(U9-OFF_NULL-Pad5)") (class "Default")
      (node (ref "U9") (pin "5") (pinfunction "OFF_NULL_5") (pintype "passive"))
    )
    (net (code "82") (name "unconnected-(U10-ACX1-Pad3)") (class "Default")
      (node (ref "U10") (pin "3") (pinfunction "ACX1_3") (pintype "passive"))
    )
    (net (code "83") (name "unconnected-(U10-ACX2-Pad1)") (class "Default")
      (node (ref "U10") (pin "1") (pinfunction "ACX2_1") (pintype "passive"))
    )
    (net (code "84") (name "unconnected-(U10-AIN3-Pad15)") (class "Default")
      (node (ref "U10") (pin "15") (pinfunction "AIN3_15") (pintype "passive"))
    )
    (net (code "85") (name "unconnected-(U10-AIN4-Pad16)") (class "Default")
      (node (ref "U10") (pin "16") (pinfunction "AIN4_16") (pintype "passive"))
    )
    (net (code "86") (name "unconnected-(U10-AINCOM-Pad8)") (class "Default")
      (node (ref "U10") (pin "8") (pinfunction "AINCOM_8") (pintype "passive"))
    )
    (net (code "87") (name "unconnected-(U10-BPDSW-Pad20)") (class "Default")
      (node (ref "U10") (pin "20") (pinfunction "BPDSW_20") (pintype "passive"))
    )
    (net (code "88") (name "unconnected-(U10-MCLK1-Pad29)") (class "Default")
      (node (ref "U10") (pin "29") (pinfunction "MCLK1_29") (pintype "passive"))
    )
    (net (code "89") (name "unconnected-(U10-MCLK2-Pad30)") (class "Default")
      (node (ref "U10") (pin "30") (pinfunction "MCLK2_30") (pintype "passive"))
    )
    (net (code "90") (name "unconnected-(U10-NC-Pad7)") (class "Default")
      (node (ref "U10") (pin "7") (pinfunction "NC_7") (pintype "passive"))
    )
    (net (code "91") (name "unconnected-(U10-NC-Pad11)") (class "Default")
      (node (ref "U10") (pin "11") (pinfunction "NC_11") (pintype "passive"))
    )
    (net (code "92") (name "unconnected-(U10-NC-Pad12)") (class "Default")
      (node (ref "U10") (pin "12") (pinfunction "NC_12") (pintype "passive"))
    )
    (net (code "93") (name "unconnected-(U10-NC-Pad13)") (class "Default")
      (node (ref "U10") (pin "13") (pinfunction "NC_13") (pintype "passive"))
    )
    (net (code "94") (name "unconnected-(U10-NC-Pad14)") (class "Default")
      (node (ref "U10") (pin "14") (pinfunction "NC_14") (pintype "passive"))
    )
    (net (code "95") (name "unconnected-(U10-NC-Pad19)") (class "Default")
      (node (ref "U10") (pin "19") (pinfunction "NC_19") (pintype "passive"))
    )
    (net (code "96") (name "unconnected-(U10-NC-Pad26)") (class "Default")
      (node (ref "U10") (pin "26") (pinfunction "NC_26") (pintype "passive"))
    )
    (net (code "97") (name "unconnected-(U10-~{ACX1}-Pad4)") (class "Default")
      (node (ref "U10") (pin "4") (pinfunction "~{ACX1}_4") (pintype "passive"))
    )
    (net (code "98") (name "unconnected-(U10-~{ACX2}-Pad2)") (class "Default")
      (node (ref "U10") (pin "2") (pinfunction "~{ACX2}_2") (pintype "passive"))
    )
    (net (code "99") (name "unconnected-(U12-NIC-Pad3)") (class "Default")
      (node (ref "U12") (pin "3") (pinfunction "NIC_3") (pintype "passive"))
    )
    (net (code "100") (name "unconnected-(U12-NIC-Pad7)") (class "Default")
      (node (ref "U12") (pin "7") (pinfunction "NIC_7") (pintype "passive"))
    )
    (net (code "101") (name "unconnected-(U12-TP-Pad1)") (class "Default")
      (node (ref "U12") (pin "1") (pinfunction "TP_1") (pintype "passive"))
    )
    (net (code "102") (name "unconnected-(U12-TP-Pad8)") (class "Default")
      (node (ref "U12") (pin "8") (pinfunction "TP_8") (pintype "passive"))
    )
    (net (code "103") (name "unconnected-(U12-TRIM-Pad5)") (class "Default")
      (node (ref "U12") (pin "5") (pinfunction "TRIM_5") (pintype "passive"))
    )
  )
)
